# ETHERNET.net
KiCad netlist of a schematic drawn in Altium Designer
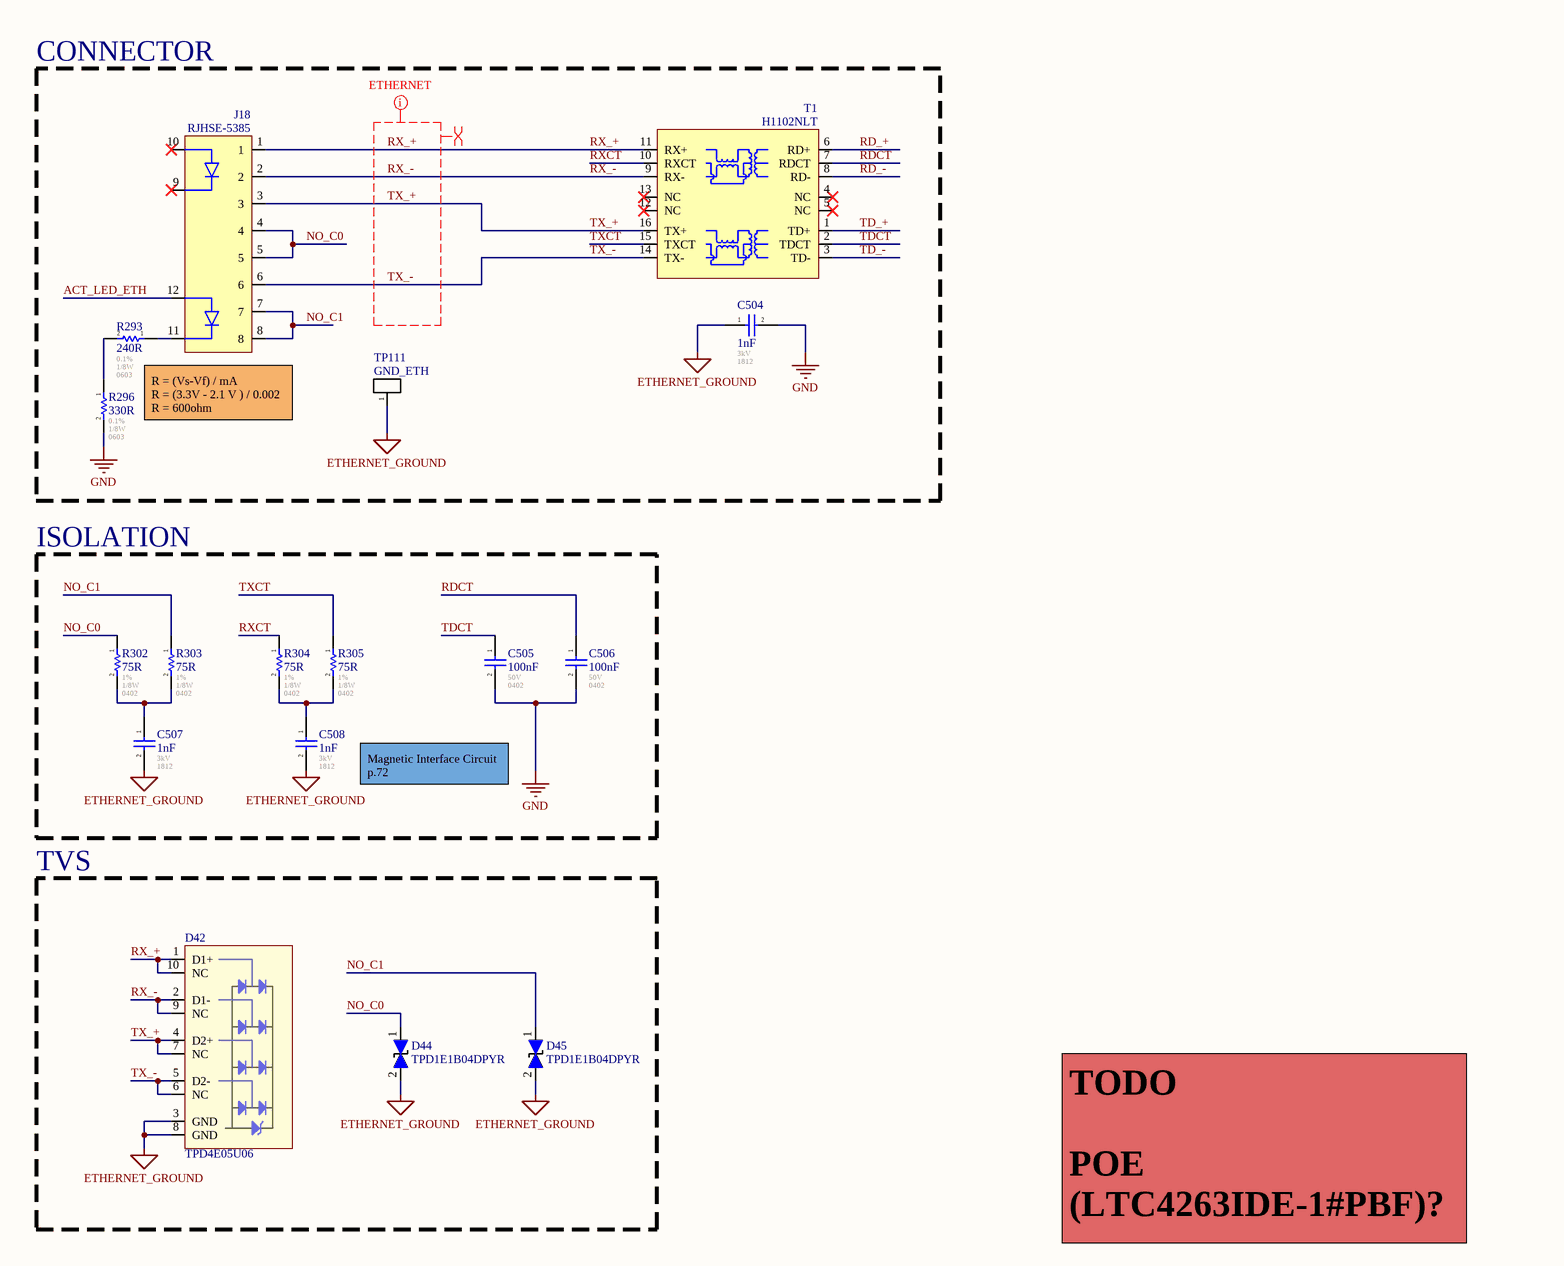
[diagram p0: ETHERNET.SchDoc, top left]
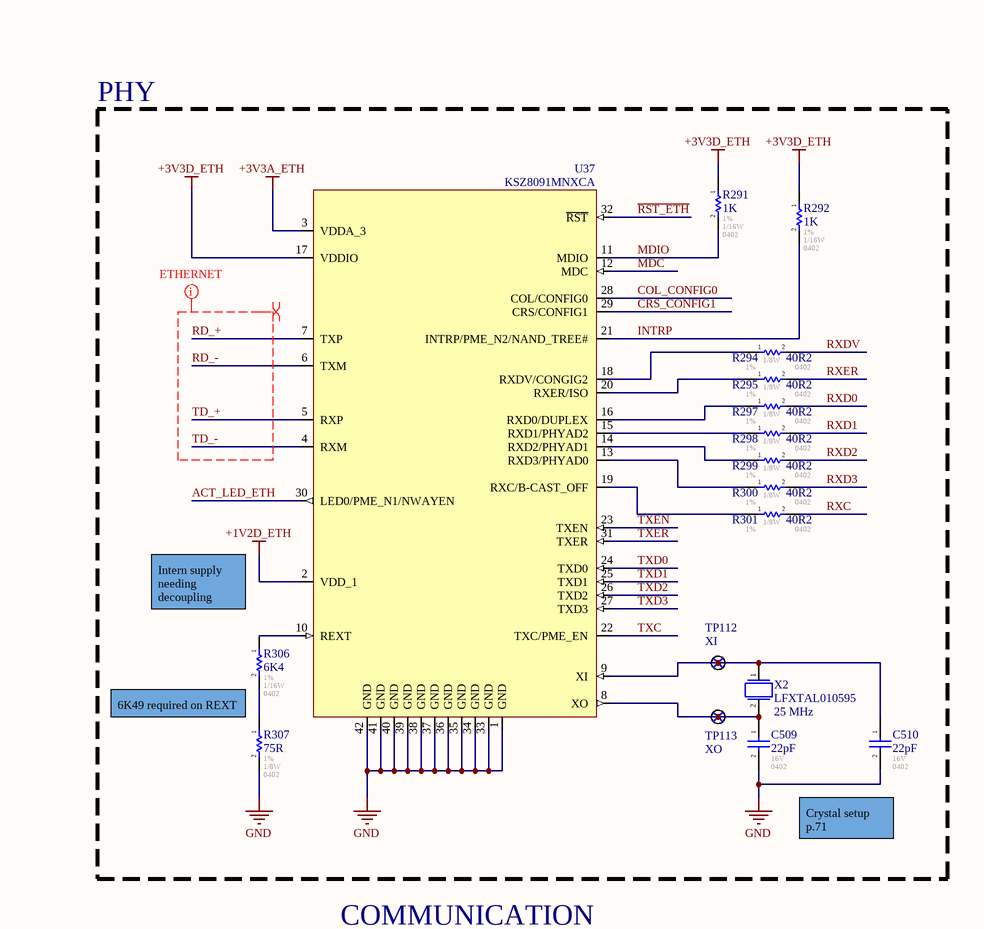
[diagram p1: ETHERNET.SchDoc, top right]
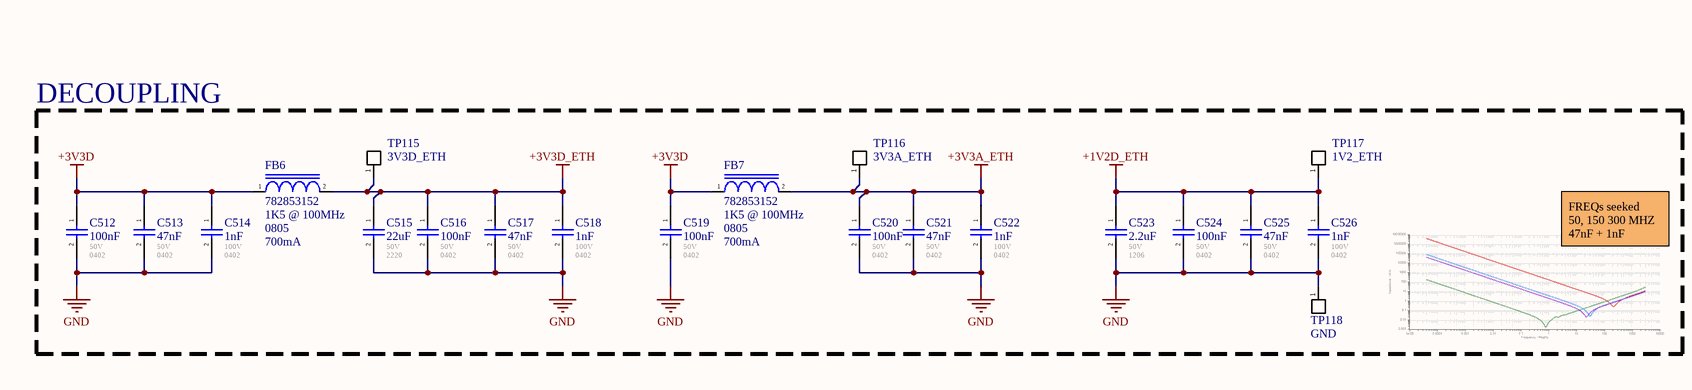
[diagram p2: ETHERNET.SchDoc, bottom left]
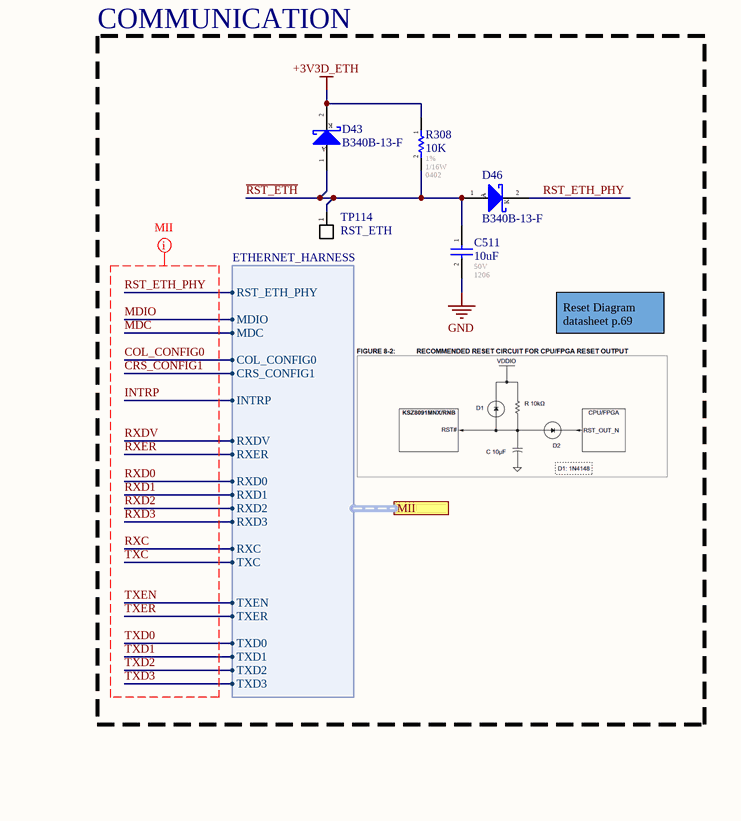
[diagram p3: ETHERNET.SchDoc, bottom right]

(export (version "E")
  (design (tool "Eeschema 10.0.6"))
  (components
    (comp (ref "C504")
      (value "1nF")
      (footprint "1812")
      (description "C1812C102KHRACAUTO\r\n0402 470pF 10% X7R Ceramic Capacitor")
      (fields
        (field (name "MFR") "KEMET")
        (field (name "PART#") "C1812C102KHRACAUTO")
        (field (name "VOLTAGE - RATED") "3kV")
      )
      (libsource (lib "Symbols") (part "CAP_CER"))
    )
    (comp (ref "C505")
      (value "100nF")
      (footprint "0402")
      (description "GCM155R71H104KE02J\r\n0402 100nF 10% X7R Ceramic Capacitor")
      (fields
        (field (name "MFR") "Murata")
        (field (name "PART#") "GCM155R71H104KE02J")
        (field (name "VOLTAGE - RATED") "50V")
      )
      (libsource (lib "Symbols") (part "CAP_CER"))
    )
    (comp (ref "C506")
      (value "100nF")
      (footprint "0402")
      (description "GCM155R71H104KE02J\r\n0402 100nF 10% X7R Ceramic Capacitor")
      (fields
        (field (name "MFR") "Murata")
        (field (name "PART#") "GCM155R71H104KE02J")
        (field (name "VOLTAGE - RATED") "50V")
      )
      (libsource (lib "Symbols") (part "CAP_CER"))
    )
    (comp (ref "C507")
      (value "1nF")
      (footprint "1812")
      (description "C1812C102KHRACAUTO\r\n0402 470pF 10% X7R Ceramic Capacitor")
      (fields
        (field (name "MFR") "KEMET")
        (field (name "PART#") "C1812C102KHRACAUTO")
        (field (name "VOLTAGE - RATED") "3kV")
      )
      (libsource (lib "Symbols") (part "CAP_CER"))
    )
    (comp (ref "C508")
      (value "1nF")
      (footprint "1812")
      (description "C1812C102KHRACAUTO\r\n0402 470pF 10% X7R Ceramic Capacitor")
      (fields
        (field (name "MFR") "KEMET")
        (field (name "PART#") "C1812C102KHRACAUTO")
        (field (name "VOLTAGE - RATED") "3kV")
      )
      (libsource (lib "Symbols") (part "CAP_CER"))
    )
    (comp (ref "C509")
      (value "22pF")
      (footprint "0402")
      (description "0402 22pF X7R Ceramic Capacitor\r\nC0402C220K4RACAUTO")
      (fields (field (name "VOLTAGE - RATED") "16V"))
      (libsource (lib "Symbols") (part "CAP_CER"))
    )
    (comp (ref "C510")
      (value "22pF")
      (footprint "0402")
      (description "0402 22pF X7R Ceramic Capacitor\r\nC0402C220K4RACAUTO")
      (fields (field (name "VOLTAGE - RATED") "16V"))
      (libsource (lib "Symbols") (part "CAP_CER"))
    )
    (comp (ref "C511")
      (value "10uF")
      (footprint "1206")
      (description "GRT31CR61H106KE01L\r\n1206 10uF 10% X5R Ceramic Capacitor")
      (fields
        (field (name "MFR") "Murata")
        (field (name "VOLTAGE - RATED") "50V")
        (field (name "TOLERANCE") "10%")
      )
      (libsource (lib "Symbols") (part "CAP_CER"))
    )
    (comp (ref "C512")
      (value "100nF")
      (footprint "0402")
      (description "GCM155R71H104KE02J\r\n0402 100nF 10% X7R Ceramic Capacitor")
      (fields
        (field (name "MFR") "Murata")
        (field (name "PART#") "GCM155R71H104KE02J")
        (field (name "VOLTAGE - RATED") "50V")
      )
      (libsource (lib "Symbols") (part "CAP_CER"))
    )
    (comp (ref "C513")
      (value "47nF")
      (footprint "0402")
      (description "GCM155R71H473KE02J\r\n0402 47nF 10% X7R Ceramic Capacitor")
      (fields
        (field (name "MFR") "Murata")
        (field (name "PART#") "GCM155R71H473KE02J")
        (field (name "VOLTAGE - RATED") "50V")
      )
      (libsource (lib "Symbols") (part "CAP_CER"))
    )
    (comp (ref "C514")
      (value "1nF")
      (footprint "0402")
      (description "GCM155R72A102KA37D\r\n0402 1nF 10% X7R Ceramic Capacitor")
      (fields
        (field (name "MFR") "Murata")
        (field (name "PART#") "GCM155R72A102KA37D")
        (field (name "VOLTAGE - RATED") "100V")
      )
      (libsource (lib "Symbols") (part "CAP_CER"))
    )
    (comp (ref "C515")
      (value "22uF")
      (footprint "2220")
      (description "CGA9P3X7R1H226M250KB\r\n2220 22uF 20% X7R Ceramic Capacitor")
      (fields
        (field (name "MFR") "TDK")
        (field (name "VOLTAGE - RATED") "50V")
        (field (name "TOLERANCE") "20%")
      )
      (libsource (lib "Symbols") (part "CAP_CER"))
    )
    (comp (ref "C516")
      (value "100nF")
      (footprint "0402")
      (description "GCM155R71H104KE02J\r\n0402 100nF 10% X7R Ceramic Capacitor")
      (fields
        (field (name "MFR") "Murata")
        (field (name "PART#") "GCM155R71H104KE02J")
        (field (name "VOLTAGE - RATED") "50V")
      )
      (libsource (lib "Symbols") (part "CAP_CER"))
    )
    (comp (ref "C517")
      (value "47nF")
      (footprint "0402")
      (description "GCM155R71H473KE02J\r\n0402 47nF 10% X7R Ceramic Capacitor")
      (fields
        (field (name "MFR") "Murata")
        (field (name "PART#") "GCM155R71H473KE02J")
        (field (name "VOLTAGE - RATED") "50V")
      )
      (libsource (lib "Symbols") (part "CAP_CER"))
    )
    (comp (ref "C518")
      (value "1nF")
      (footprint "0402")
      (description "GCM155R72A102KA37D\r\n0402 1nF 10% X7R Ceramic Capacitor")
      (fields
        (field (name "MFR") "Murata")
        (field (name "PART#") "GCM155R72A102KA37D")
        (field (name "VOLTAGE - RATED") "100V")
      )
      (libsource (lib "Symbols") (part "CAP_CER"))
    )
    (comp (ref "C519")
      (value "100nF")
      (footprint "0402")
      (description "GCM155R71H104KE02J\r\n0402 100nF 10% X7R Ceramic Capacitor")
      (fields
        (field (name "MFR") "Murata")
        (field (name "PART#") "GCM155R71H104KE02J")
        (field (name "VOLTAGE - RATED") "50V")
      )
      (libsource (lib "Symbols") (part "CAP_CER"))
    )
    (comp (ref "C520")
      (value "100nF")
      (footprint "0402")
      (description "GCM155R71H104KE02J\r\n0402 100nF 10% X7R Ceramic Capacitor")
      (fields
        (field (name "MFR") "Murata")
        (field (name "PART#") "GCM155R71H104KE02J")
        (field (name "VOLTAGE - RATED") "50V")
      )
      (libsource (lib "Symbols") (part "CAP_CER"))
    )
    (comp (ref "C521")
      (value "47nF")
      (footprint "0402")
      (description "GCM155R71H473KE02J\r\n0402 47nF 10% X7R Ceramic Capacitor")
      (fields
        (field (name "MFR") "Murata")
        (field (name "PART#") "GCM155R71H473KE02J")
        (field (name "VOLTAGE - RATED") "50V")
      )
      (libsource (lib "Symbols") (part "CAP_CER"))
    )
    (comp (ref "C522")
      (value "1nF")
      (footprint "0402")
      (description "GCM155R72A102KA37D\r\n0402 1nF 10% X7R Ceramic Capacitor")
      (fields
        (field (name "MFR") "Murata")
        (field (name "PART#") "GCM155R72A102KA37D")
        (field (name "VOLTAGE - RATED") "100V")
      )
      (libsource (lib "Symbols") (part "CAP_CER"))
    )
    (comp (ref "C523")
      (value "2.2uF")
      (footprint "1206")
      (description "GRT31CR71H225KE13L\r\n1206 2.2uF 10% X7R Ceramic Capacitor")
      (fields
        (field (name "MFR") "Murata")
        (field (name "PART#") "GRT31CR71H225KE13L")
        (field (name "VOLTAGE - RATED") "50V")
      )
      (libsource (lib "Symbols") (part "CAP_CER"))
    )
    (comp (ref "C524")
      (value "100nF")
      (footprint "0402")
      (description "GCM155R71H104KE02J\r\n0402 100nF 10% X7R Ceramic Capacitor")
      (fields
        (field (name "MFR") "Murata")
        (field (name "PART#") "GCM155R71H104KE02J")
        (field (name "VOLTAGE - RATED") "50V")
      )
      (libsource (lib "Symbols") (part "CAP_CER"))
    )
    (comp (ref "C525")
      (value "47nF")
      (footprint "0402")
      (description "GCM155R71H473KE02J\r\n0402 47nF 10% X7R Ceramic Capacitor")
      (fields
        (field (name "MFR") "Murata")
        (field (name "PART#") "GCM155R71H473KE02J")
        (field (name "VOLTAGE - RATED") "50V")
      )
      (libsource (lib "Symbols") (part "CAP_CER"))
    )
    (comp (ref "C526")
      (value "1nF")
      (footprint "0402")
      (description "GCM155R72A102KA37D\r\n0402 1nF 10% X7R Ceramic Capacitor")
      (fields
        (field (name "MFR") "Murata")
        (field (name "PART#") "GCM155R72A102KA37D")
        (field (name "VOLTAGE - RATED") "100V")
      )
      (libsource (lib "Symbols") (part "CAP_CER"))
    )
    (comp (ref "D42")
      (value "TPD4E05U06")
      (footprint "TVS_DATA_TPD4E05U06")
      (description "TVS - TVS DIODE 5.5VWM 14VC - 10SON")
      (fields
        (field (name "CREATEDBY/DATE") "Olivier Bernard / 12/3/2018")
        (field (name "VERIFIEDBY") "Caroline Paulin / 4 juillet 2018")
      )
      (libsource (lib "S7CAS_LIB2023") (part "TVS_DATA_TPD4E05U06"))
    )
    (comp (ref "D43")
      (value "B340B-13-F")
      (footprint "DO214AA (SMB)")
      (description "VS-15MQ040HM3/5AT")
      (libsource (lib "Symbols") (part "DIODE_SHOTTKEY"))
    )
    (comp (ref "D44")
      (value "TPD1E1B04DPYR")
      (footprint "TVS_DATA_TPD1E1B04DPYR")
      (description "TVS - TVS DIODE 3.6V 8.5V - 0402")
      (fields
        (field (name "CREATEDBY/DATE") "Keven Deslandes - 2018/10/19")
        (field (name "VERIFIEDBY") "Caroline Paulin - 28 janv 2019")
      )
      (libsource (lib "S7CAS_LIB2023") (part "TVS_DATA_TPD1E1B04DPYR"))
    )
    (comp (ref "D45")
      (value "TPD1E1B04DPYR")
      (footprint "TVS_DATA_TPD1E1B04DPYR")
      (description "TVS - TVS DIODE 3.6V 8.5V - 0402")
      (fields
        (field (name "CREATEDBY/DATE") "Keven Deslandes - 2018/10/19")
        (field (name "VERIFIEDBY") "Caroline Paulin - 28 janv 2019")
      )
      (libsource (lib "S7CAS_LIB2023") (part "TVS_DATA_TPD1E1B04DPYR"))
    )
    (comp (ref "D46")
      (value "B340B-13-F")
      (footprint "DO214AA (SMB)")
      (description "VS-15MQ040HM3/5AT")
      (libsource (lib "Symbols") (part "DIODE_SHOTTKEY"))
    )
    (comp (ref "FB6")
      (value "782853152")
      (footprint "IND_0805")
      (description "600 Ohms @ 100 MHz 1 Signal Line Ferrite Bead 0603 (1608 Metric) 1A 200mOhm")
      (fields
        (field (name "IMPEDANCE @ FREQ") "1K5 @ 100MHz")
        (field (name "PACKAGE / CASE") "0805")
        (field (name "CURRENT RATING") "700mA")
        (field (name "MANUFACTURER") "Wurth Elektronik")
      )
      (libsource (lib "Symbols") (part "FERRITE_BEAD"))
    )
    (comp (ref "FB7")
      (value "782853152")
      (footprint "IND_0805")
      (description "600 Ohms @ 100 MHz 1 Signal Line Ferrite Bead 0603 (1608 Metric) 1A 200mOhm")
      (fields
        (field (name "IMPEDANCE @ FREQ") "1K5 @ 100MHz")
        (field (name "PACKAGE / CASE") "0805")
        (field (name "CURRENT RATING") "700mA")
        (field (name "MANUFACTURER") "Wurth Elektronik")
      )
      (libsource (lib "Symbols") (part "FERRITE_BEAD"))
    )
    (comp (ref "J18")
      (value "RJHSE-5385")
      (footprint "CONN_ETHERNET_RJHSE-5385")
      (description "CONN - MOD JACK RJ45 R/A ETHERNET - TH")
      (fields (field (name "MFG") "Amphenol") (field (name "CREATEDBY") "Jonathan Bouchard"))
      (libsource (lib "S7CAS_LIB2023") (part "CONN_ETHERNET_RJHSE-5385"))
    )
    (comp (ref "R291")
      (value "1K")
      (footprint "RES_0402")
      (fields
        (field (name "TOLERANCE") "1%")
        (field (name "POWER") "1/16W")
        (field (name "PACKAGE / CASE") "0402")
      )
      (libsource (lib "Symbols") (part "RESISTOR"))
    )
    (comp (ref "R292")
      (value "1K")
      (footprint "RES_0402")
      (fields
        (field (name "TOLERANCE") "1%")
        (field (name "POWER") "1/16W")
        (field (name "PACKAGE / CASE") "0402")
      )
      (libsource (lib "Symbols") (part "RESISTOR"))
    )
    (comp (ref "R293")
      (value "240R")
      (footprint "RES_0603")
      (fields
        (field (name "TOLERANCE") "0.1%")
        (field (name "POWER") "1/8W")
        (field (name "PACKAGE / CASE") "0603")
      )
      (libsource (lib "Symbols") (part "RESISTOR"))
    )
    (comp (ref "R294")
      (value "40R2")
      (footprint "RES_0402")
      (fields
        (field (name "TOLERANCE") "1%")
        (field (name "POWER") "1/8W")
        (field (name "PACKAGE / CASE") "0402")
      )
      (libsource (lib "Symbols") (part "RESISTOR"))
    )
    (comp (ref "R295")
      (value "40R2")
      (footprint "RES_0402")
      (fields
        (field (name "TOLERANCE") "1%")
        (field (name "POWER") "1/8W")
        (field (name "PACKAGE / CASE") "0402")
      )
      (libsource (lib "Symbols") (part "RESISTOR"))
    )
    (comp (ref "R296")
      (value "330R")
      (footprint "RES_0603")
      (description "1M 0603 1% 1/16W Resistor")
      (fields
        (field (name "TOLERANCE") "0.1%")
        (field (name "POWER") "1/8W")
        (field (name "PACKAGE / CASE") "0603")
      )
      (libsource (lib "Symbols") (part "RESISTOR"))
    )
    (comp (ref "R297")
      (value "40R2")
      (footprint "RES_0402")
      (fields
        (field (name "TOLERANCE") "1%")
        (field (name "POWER") "1/8W")
        (field (name "PACKAGE / CASE") "0402")
      )
      (libsource (lib "Symbols") (part "RESISTOR"))
    )
    (comp (ref "R298")
      (value "40R2")
      (footprint "RES_0402")
      (fields
        (field (name "TOLERANCE") "1%")
        (field (name "POWER") "1/8W")
        (field (name "PACKAGE / CASE") "0402")
      )
      (libsource (lib "Symbols") (part "RESISTOR"))
    )
    (comp (ref "R299")
      (value "40R2")
      (footprint "RES_0402")
      (fields
        (field (name "TOLERANCE") "1%")
        (field (name "POWER") "1/8W")
        (field (name "PACKAGE / CASE") "0402")
      )
      (libsource (lib "Symbols") (part "RESISTOR"))
    )
    (comp (ref "R300")
      (value "40R2")
      (footprint "RES_0402")
      (fields
        (field (name "TOLERANCE") "1%")
        (field (name "POWER") "1/8W")
        (field (name "PACKAGE / CASE") "0402")
      )
      (libsource (lib "Symbols") (part "RESISTOR"))
    )
    (comp (ref "R301")
      (value "40R2")
      (footprint "RES_0402")
      (fields
        (field (name "TOLERANCE") "1%")
        (field (name "POWER") "1/8W")
        (field (name "PACKAGE / CASE") "0402")
      )
      (libsource (lib "Symbols") (part "RESISTOR"))
    )
    (comp (ref "R302")
      (value "75R")
      (footprint "RES_0402")
      (fields
        (field (name "TOLERANCE") "1%")
        (field (name "POWER") "1/8W")
        (field (name "PACKAGE / CASE") "0402")
      )
      (libsource (lib "Symbols") (part "RESISTOR"))
    )
    (comp (ref "R303")
      (value "75R")
      (footprint "RES_0402")
      (fields
        (field (name "TOLERANCE") "1%")
        (field (name "POWER") "1/8W")
        (field (name "PACKAGE / CASE") "0402")
      )
      (libsource (lib "Symbols") (part "RESISTOR"))
    )
    (comp (ref "R304")
      (value "75R")
      (footprint "RES_0402")
      (fields
        (field (name "TOLERANCE") "1%")
        (field (name "POWER") "1/8W")
        (field (name "PACKAGE / CASE") "0402")
      )
      (libsource (lib "Symbols") (part "RESISTOR"))
    )
    (comp (ref "R305")
      (value "75R")
      (footprint "RES_0402")
      (fields
        (field (name "TOLERANCE") "1%")
        (field (name "POWER") "1/8W")
        (field (name "PACKAGE / CASE") "0402")
      )
      (libsource (lib "Symbols") (part "RESISTOR"))
    )
    (comp (ref "R306")
      (value "6K4")
      (footprint "RES_0402")
      (fields
        (field (name "TOLERANCE") "1%")
        (field (name "POWER") "1/16W")
        (field (name "PACKAGE / CASE") "0402")
      )
      (libsource (lib "Symbols") (part "RESISTOR"))
    )
    (comp (ref "R307")
      (value "75R")
      (footprint "RES_0402")
      (fields
        (field (name "TOLERANCE") "1%")
        (field (name "POWER") "1/8W")
        (field (name "PACKAGE / CASE") "0402")
      )
      (libsource (lib "Symbols") (part "RESISTOR"))
    )
    (comp (ref "R308")
      (value "10K")
      (footprint "RES_0402")
      (fields
        (field (name "TOLERANCE") "1%")
        (field (name "POWER") "1/16W")
        (field (name "PACKAGE / CASE") "0402")
      )
      (libsource (lib "Symbols") (part "RESISTOR"))
    )
    (comp (ref "T1")
      (value "H1102NLT")
      (footprint "TRANSFO_H1102NLT")
      (description "TRANSFO - ETHERNET 10/100B-TX - SMD-16")
      (fields (field (name "MFG") "Pulse Eng.") (field (name "CREATEDBY") "Jonathan Bouchard"))
      (libsource (lib "S7CAS_LIB2023") (part "TRANSFO_H1102NLT"))
    )
    (comp (ref "TP111")
      (value "GND_ETH")
      (footprint "TP_HOLE")
      (description "Test Point")
      (libsource (lib "Symbols") (part "TESTPOINT"))
    )
    (comp (ref "TP112")
      (value "XI")
      (footprint "TP_PAD_TINY")
      (description "Test Point")
      (libsource (lib "Symbols") (part "TESTPOINT_PAD_TINY"))
    )
    (comp (ref "TP113")
      (value "XO")
      (footprint "TP_PAD_TINY")
      (description "Test Point")
      (libsource (lib "Symbols") (part "TESTPOINT_PAD_TINY"))
    )
    (comp (ref "TP114")
      (value "RST_ETH")
      (footprint "TP_PAD")
      (description "Test Point")
      (libsource (lib "Symbols") (part "TESTPOINT_PAD"))
    )
    (comp (ref "TP115")
      (value "3V3D_ETH")
      (footprint "TP_PAD")
      (description "Test Point")
      (libsource (lib "Symbols") (part "TESTPOINT_PAD"))
    )
    (comp (ref "TP116")
      (value "3V3A_ETH")
      (footprint "TP_PAD")
      (description "Test Point")
      (libsource (lib "Symbols") (part "TESTPOINT_PAD"))
    )
    (comp (ref "TP117")
      (value "1V2_ETH")
      (footprint "TP_PAD")
      (description "Test Point")
      (libsource (lib "Symbols") (part "TESTPOINT_PAD"))
    )
    (comp (ref "TP118")
      (value "GND")
      (footprint "TP_PAD")
      (description "Test Point")
      (libsource (lib "Symbols") (part "TESTPOINT_PAD"))
    )
    (comp (ref "U37")
      (value "KSZ8091MNXCA")
      (footprint "COM_ETH_PHY_KSZ8091MNXCA")
      (description "COM - ETHERNET PHY 10/100 - QFN-32")
      (fields
        (field (name "VOLTAGE") "1.8V, 2.5V, 3.3V")
        (field (name "MFG") "Micrel")
        (field (name "CREATEDBY") "Jonathan Bouchard")
      )
      (libsource (lib "S7CAS_LIB2023") (part "COM_ETH_PHY_KSZ8091MNXCA"))
    )
    (comp (ref "X2")
      (value "LFXTAL010595")
      (footprint "HC49_SMD")
      (description "25 MHz ±30ppm Crystal 16pF 40 Ohms HC-49/US")
      (fields (field (name "FREQUENCY") "25 MHz"))
      (libsource (lib "Symbols") (part "OSCILLATOR"))
    )
  )
  (nets
    (net (code "2") (name "+1V2D_ETH") (class "Default")
      (node (ref "C523") (pin "1") (pinfunction "1_1") (pintype "passive"))
      (node (ref "C524") (pin "1") (pinfunction "1_1") (pintype "passive"))
      (node (ref "C525") (pin "1") (pinfunction "1_1") (pintype "passive"))
      (node (ref "C526") (pin "1") (pinfunction "1_1") (pintype "passive"))
      (node (ref "TP117") (pin "1") (pinfunction "A_1") (pintype "passive"))
      (node (ref "U37") (pin "2") (pinfunction "VDD_1_2") (pintype "power_in"))
    )
    (net (code "3") (name "+3V3A_ETH") (class "Default")
      (node (ref "C520") (pin "1") (pinfunction "1_1") (pintype "passive"))
      (node (ref "C521") (pin "1") (pinfunction "1_1") (pintype "passive"))
      (node (ref "C522") (pin "1") (pinfunction "1_1") (pintype "passive"))
      (node (ref "FB7") (pin "2") (pinfunction "2_2") (pintype "passive"))
      (node (ref "TP116") (pin "1") (pinfunction "A_1") (pintype "passive"))
      (node (ref "U37") (pin "3") (pinfunction "VDDA_3_3") (pintype "power_in"))
    )
    (net (code "4") (name "+3V3D") (class "Default")
      (node (ref "C512") (pin "1") (pinfunction "1_1") (pintype "passive"))
      (node (ref "C513") (pin "1") (pinfunction "1_1") (pintype "passive"))
      (node (ref "C514") (pin "1") (pinfunction "1_1") (pintype "passive"))
      (node (ref "C519") (pin "1") (pinfunction "1_1") (pintype "passive"))
      (node (ref "FB6") (pin "1") (pinfunction "1_1") (pintype "passive"))
      (node (ref "FB7") (pin "1") (pinfunction "1_1") (pintype "passive"))
    )
    (net (code "5") (name "+3V3D_ETH") (class "Default")
      (node (ref "C515") (pin "1") (pinfunction "1_1") (pintype "passive"))
      (node (ref "C516") (pin "1") (pinfunction "1_1") (pintype "passive"))
      (node (ref "C517") (pin "1") (pinfunction "1_1") (pintype "passive"))
      (node (ref "C518") (pin "1") (pinfunction "1_1") (pintype "passive"))
      (node (ref "D43") (pin "2") (pinfunction "K_2") (pintype "passive"))
      (node (ref "FB6") (pin "2") (pinfunction "2_2") (pintype "passive"))
      (node (ref "R291") (pin "1") (pinfunction "1_1") (pintype "passive"))
      (node (ref "R292") (pin "1") (pinfunction "1_1") (pintype "passive"))
      (node (ref "R308") (pin "1") (pinfunction "1_1") (pintype "passive"))
      (node (ref "TP115") (pin "1") (pinfunction "A_1") (pintype "passive"))
      (node (ref "U37") (pin "17") (pinfunction "VDDIO_17") (pintype "power_in"))
    )
    (net (code "6") (name "/ACT_LED_ETH") (class "Default")
      (node (ref "J18") (pin "12") (pinfunction "LED2_A_12") (pintype "passive"))
      (node (ref "U37") (pin "30") (pinfunction "LED0/PME_N1/NWAYEN_30") (pintype "output"))
    )
    (net (code "7") (name "/COL_CONFIG0") (class "Default")
      (node (ref "U37") (pin "28") (pinfunction "COL/CONFIG0_28") (pintype "bidirectional"))
    )
    (net (code "8") (name "/CRS_CONFIG1") (class "Default")
      (node (ref "U37") (pin "29") (pinfunction "CRS/CONFIG1_29") (pintype "bidirectional"))
    )
    (net (code "9") (name "/INTRP") (class "Default")
      (node (ref "R292") (pin "2") (pinfunction "2_2") (pintype "passive"))
      (node (ref "U37") (pin "21") (pinfunction "INTRP/PME_N2/NAND_TREE#_21") (pintype "bidirectional"))
    )
    (net (code "10") (name "/MDC") (class "Default")
      (node (ref "U37") (pin "12") (pinfunction "MDC_12") (pintype "input"))
    )
    (net (code "11") (name "/MDIO") (class "Default")
      (node (ref "R291") (pin "2") (pinfunction "2_2") (pintype "passive"))
      (node (ref "U37") (pin "11") (pinfunction "MDIO_11") (pintype "bidirectional"))
    )
    (net (code "12") (name "/NO_C0") (class "Default")
      (node (ref "D44") (pin "1") (pinfunction "i/o_1") (pintype "passive"))
      (node (ref "J18") (pin "4") (pinfunction "4_4") (pintype "passive"))
      (node (ref "J18") (pin "5") (pinfunction "5_5") (pintype "passive"))
      (node (ref "R302") (pin "1") (pinfunction "1_1") (pintype "passive"))
    )
    (net (code "13") (name "/NO_C1") (class "Default")
      (node (ref "D45") (pin "1") (pinfunction "i/o_1") (pintype "passive"))
      (node (ref "J18") (pin "7") (pinfunction "7_7") (pintype "passive"))
      (node (ref "J18") (pin "8") (pinfunction "8_8") (pintype "passive"))
      (node (ref "R303") (pin "1") (pinfunction "1_1") (pintype "passive"))
    )
    (net (code "14") (name "/RDCT") (class "Default")
      (node (ref "C506") (pin "1") (pinfunction "1_1") (pintype "passive"))
      (node (ref "T1") (pin "7") (pinfunction "RDCT_7") (pintype "passive"))
    )
    (net (code "15") (name "/RD_+") (class "Default")
      (node (ref "T1") (pin "6") (pinfunction "RD+_6") (pintype "passive"))
      (node (ref "U37") (pin "7") (pinfunction "TXP_7") (pintype "bidirectional"))
    )
    (net (code "16") (name "/RD_-") (class "Default")
      (node (ref "T1") (pin "8") (pinfunction "RD-_8") (pintype "passive"))
      (node (ref "U37") (pin "6") (pinfunction "TXM_6") (pintype "bidirectional"))
    )
    (net (code "17") (name "/RST_ETH") (class "Default")
      (node (ref "C511") (pin "1") (pinfunction "1_1") (pintype "passive"))
      (node (ref "D43") (pin "1") (pinfunction "A_1") (pintype "passive"))
      (node (ref "D46") (pin "1") (pinfunction "A_1") (pintype "passive"))
      (node (ref "R308") (pin "2") (pinfunction "2_2") (pintype "passive"))
      (node (ref "TP114") (pin "1") (pinfunction "A_1") (pintype "passive"))
      (node (ref "U37") (pin "32") (pinfunction "RST_32") (pintype "input"))
    )
    (net (code "18") (name "/RST_ETH_PHY") (class "Default")
      (node (ref "D46") (pin "2") (pinfunction "K_2") (pintype "passive"))
    )
    (net (code "19") (name "/RXC") (class "Default")
      (node (ref "R301") (pin "2") (pinfunction "2_2") (pintype "passive"))
    )
    (net (code "20") (name "/RXCT") (class "Default")
      (node (ref "R304") (pin "1") (pinfunction "1_1") (pintype "passive"))
      (node (ref "T1") (pin "10") (pinfunction "RXCT_10") (pintype "passive"))
    )
    (net (code "21") (name "/RXD0") (class "Default")
      (node (ref "R297") (pin "2") (pinfunction "2_2") (pintype "passive"))
    )
    (net (code "22") (name "/RXD1") (class "Default")
      (node (ref "R298") (pin "2") (pinfunction "2_2") (pintype "passive"))
    )
    (net (code "23") (name "/RXD2") (class "Default")
      (node (ref "R299") (pin "2") (pinfunction "2_2") (pintype "passive"))
    )
    (net (code "24") (name "/RXD3") (class "Default")
      (node (ref "R300") (pin "2") (pinfunction "2_2") (pintype "passive"))
    )
    (net (code "25") (name "/RXDV") (class "Default")
      (node (ref "R294") (pin "2") (pinfunction "2_2") (pintype "passive"))
    )
    (net (code "26") (name "/RXER") (class "Default")
      (node (ref "R295") (pin "2") (pinfunction "2_2") (pintype "passive"))
    )
    (net (code "27") (name "/RX_+") (class "Default")
      (node (ref "D42") (pin "1") (pinfunction "D1+_1") (pintype "passive"))
      (node (ref "D42") (pin "10") (pinfunction "NC_10") (pintype "passive"))
      (node (ref "J18") (pin "1") (pinfunction "1_1") (pintype "passive"))
      (node (ref "T1") (pin "11") (pinfunction "RX+_11") (pintype "passive"))
    )
    (net (code "28") (name "/RX_-") (class "Default")
      (node (ref "D42") (pin "2") (pinfunction "D1-_2") (pintype "passive"))
      (node (ref "D42") (pin "9") (pinfunction "NC_9") (pintype "passive"))
      (node (ref "J18") (pin "2") (pinfunction "2_2") (pintype "passive"))
      (node (ref "T1") (pin "9") (pinfunction "RX-_9") (pintype "passive"))
    )
    (net (code "29") (name "/TDCT") (class "Default")
      (node (ref "C505") (pin "1") (pinfunction "1_1") (pintype "passive"))
      (node (ref "T1") (pin "2") (pinfunction "TDCT_2") (pintype "passive"))
    )
    (net (code "30") (name "/TD_+") (class "Default")
      (node (ref "T1") (pin "1") (pinfunction "TD+_1") (pintype "passive"))
      (node (ref "U37") (pin "5") (pinfunction "RXP_5") (pintype "bidirectional"))
    )
    (net (code "31") (name "/TD_-") (class "Default")
      (node (ref "T1") (pin "3") (pinfunction "TD-_3") (pintype "passive"))
      (node (ref "U37") (pin "4") (pinfunction "RXM_4") (pintype "bidirectional"))
    )
    (net (code "32") (name "/TXC") (class "Default")
      (node (ref "U37") (pin "22") (pinfunction "TXC/PME_EN_22") (pintype "bidirectional"))
    )
    (net (code "33") (name "/TXCT") (class "Default")
      (node (ref "R305") (pin "1") (pinfunction "1_1") (pintype "passive"))
      (node (ref "T1") (pin "15") (pinfunction "TXCT_15") (pintype "passive"))
    )
    (net (code "34") (name "/TXD0") (class "Default")
      (node (ref "U37") (pin "24") (pinfunction "TXD0_24") (pintype "input"))
    )
    (net (code "35") (name "/TXD1") (class "Default")
      (node (ref "U37") (pin "25") (pinfunction "TXD1_25") (pintype "input"))
    )
    (net (code "36") (name "/TXD2") (class "Default")
      (node (ref "U37") (pin "26") (pinfunction "TXD2_26") (pintype "input"))
    )
    (net (code "37") (name "/TXD3") (class "Default")
      (node (ref "U37") (pin "27") (pinfunction "TXD3_27") (pintype "input"))
    )
    (net (code "38") (name "/TXEN") (class "Default")
      (node (ref "U37") (pin "23") (pinfunction "TXEN_23") (pintype "input"))
    )
    (net (code "39") (name "/TXER") (class "Default")
      (node (ref "U37") (pin "31") (pinfunction "TXER_31") (pintype "input"))
    )
    (net (code "40") (name "/TX_+") (class "Default")
      (node (ref "D42") (pin "4") (pinfunction "D2+_4") (pintype "passive"))
      (node (ref "D42") (pin "7") (pinfunction "NC_7") (pintype "passive"))
      (node (ref "J18") (pin "3") (pinfunction "3_3") (pintype "passive"))
      (node (ref "T1") (pin "16") (pinfunction "TX+_16") (pintype "passive"))
    )
    (net (code "41") (name "/TX_-") (class "Default")
      (node (ref "D42") (pin "5") (pinfunction "D2-_5") (pintype "passive"))
      (node (ref "D42") (pin "6") (pinfunction "NC_6") (pintype "passive"))
      (node (ref "J18") (pin "6") (pinfunction "6_6") (pintype "passive"))
      (node (ref "T1") (pin "14") (pinfunction "TX-_14") (pintype "passive"))
    )
    (net (code "43") (name "ETHERNET_GROUND") (class "Default")
      (node (ref "C504") (pin "1") (pinfunction "1_1") (pintype "passive"))
      (node (ref "C507") (pin "2") (pinfunction "2_2") (pintype "passive"))
      (node (ref "C508") (pin "2") (pinfunction "2_2") (pintype "passive"))
      (node (ref "D42") (pin "3") (pinfunction "GND_3") (pintype "passive"))
      (node (ref "D42") (pin "8") (pinfunction "GND_8") (pintype "passive"))
      (node (ref "D44") (pin "2") (pinfunction "i/o_2") (pintype "passive"))
      (node (ref "D45") (pin "2") (pinfunction "i/o_2") (pintype "passive"))
      (node (ref "TP111") (pin "1") (pinfunction "A_1") (pintype "passive"))
    )
    (net (code "44") (name "GND") (class "Default")
      (node (ref "C504") (pin "2") (pinfunction "2_2") (pintype "passive"))
      (node (ref "C505") (pin "2") (pinfunction "2_2") (pintype "passive"))
      (node (ref "C506") (pin "2") (pinfunction "2_2") (pintype "passive"))
      (node (ref "C509") (pin "2") (pinfunction "2_2") (pintype "passive"))
      (node (ref "C510") (pin "2") (pinfunction "2_2") (pintype "passive"))
      (node (ref "C511") (pin "2") (pinfunction "2_2") (pintype "passive"))
      (node (ref "C512") (pin "2") (pinfunction "2_2") (pintype "passive"))
      (node (ref "C513") (pin "2") (pinfunction "2_2") (pintype "passive"))
      (node (ref "C514") (pin "2") (pinfunction "2_2") (pintype "passive"))
      (node (ref "C515") (pin "2") (pinfunction "2_2") (pintype "passive"))
      (node (ref "C516") (pin "2") (pinfunction "2_2") (pintype "passive"))
      (node (ref "C517") (pin "2") (pinfunction "2_2") (pintype "passive"))
      (node (ref "C518") (pin "2") (pinfunction "2_2") (pintype "passive"))
      (node (ref "C519") (pin "2") (pinfunction "2_2") (pintype "passive"))
      (node (ref "C520") (pin "2") (pinfunction "2_2") (pintype "passive"))
      (node (ref "C521") (pin "2") (pinfunction "2_2") (pintype "passive"))
      (node (ref "C522") (pin "2") (pinfunction "2_2") (pintype "passive"))
      (node (ref "C523") (pin "2") (pinfunction "2_2") (pintype "passive"))
      (node (ref "C524") (pin "2") (pinfunction "2_2") (pintype "passive"))
      (node (ref "C525") (pin "2") (pinfunction "2_2") (pintype "passive"))
      (node (ref "C526") (pin "2") (pinfunction "2_2") (pintype "passive"))
      (node (ref "R296") (pin "2") (pinfunction "2_2") (pintype "passive"))
      (node (ref "R307") (pin "2") (pinfunction "2_2") (pintype "passive"))
      (node (ref "TP118") (pin "1") (pinfunction "A_1") (pintype "passive"))
      (node (ref "U37") (pin "1") (pinfunction "GND_1") (pintype "power_in"))
      (node (ref "U37") (pin "33") (pinfunction "GND_33") (pintype "power_in"))
      (node (ref "U37") (pin "34") (pinfunction "GND_34") (pintype "power_in"))
      (node (ref "U37") (pin "35") (pinfunction "GND_35") (pintype "power_in"))
      (node (ref "U37") (pin "36") (pinfunction "GND_36") (pintype "power_in"))
      (node (ref "U37") (pin "37") (pinfunction "GND_37") (pintype "power_in"))
      (node (ref "U37") (pin "38") (pinfunction "GND_38") (pintype "power_in"))
      (node (ref "U37") (pin "39") (pinfunction "GND_39") (pintype "power_in"))
      (node (ref "U37") (pin "40") (pinfunction "GND_40") (pintype "power_in"))
      (node (ref "U37") (pin "41") (pinfunction "GND_41") (pintype "power_in"))
      (node (ref "U37") (pin "42") (pinfunction "GND_42") (pintype "power_in"))
    )
    (net (code "45") (name "Net-(C507-Pad1)") (class "Default")
      (node (ref "C507") (pin "1") (pinfunction "1_1") (pintype "passive"))
      (node (ref "R302") (pin "2") (pinfunction "2_2") (pintype "passive"))
      (node (ref "R303") (pin "2") (pinfunction "2_2") (pintype "passive"))
    )
    (net (code "46") (name "Net-(C508-Pad1)") (class "Default")
      (node (ref "C508") (pin "1") (pinfunction "1_1") (pintype "passive"))
      (node (ref "R304") (pin "2") (pinfunction "2_2") (pintype "passive"))
      (node (ref "R305") (pin "2") (pinfunction "2_2") (pintype "passive"))
    )
    (net (code "47") (name "Net-(J18-LED2_K)") (class "Default")
      (node (ref "J18") (pin "11") (pinfunction "LED2_K_11") (pintype "passive"))
      (node (ref "R293") (pin "1") (pinfunction "1_1") (pintype "passive"))
    )
    (net (code "48") (name "Net-(R293-Pad2)") (class "Default")
      (node (ref "R293") (pin "2") (pinfunction "2_2") (pintype "passive"))
      (node (ref "R296") (pin "1") (pinfunction "1_1") (pintype "passive"))
    )
    (net (code "49") (name "Net-(R306-Pad2)") (class "Default")
      (node (ref "R306") (pin "2") (pinfunction "2_2") (pintype "passive"))
      (node (ref "R307") (pin "1") (pinfunction "1_1") (pintype "passive"))
    )
    (net (code "50") (name "Net-(TP112-A)") (class "Default")
      (node (ref "C510") (pin "1") (pinfunction "1_1") (pintype "passive"))
      (node (ref "TP112") (pin "1") (pinfunction "A_1") (pintype "passive"))
      (node (ref "U37") (pin "9") (pinfunction "XI_9") (pintype "input"))
      (node (ref "X2") (pin "1") (pinfunction "1_1") (pintype "passive"))
    )
    (net (code "51") (name "Net-(TP113-A)") (class "Default")
      (node (ref "C509") (pin "1") (pinfunction "1_1") (pintype "passive"))
      (node (ref "TP113") (pin "1") (pinfunction "A_1") (pintype "passive"))
      (node (ref "U37") (pin "8") (pinfunction "XO_8") (pintype "output"))
      (node (ref "X2") (pin "2") (pinfunction "2_2") (pintype "passive"))
    )
    (net (code "52") (name "Net-(U37-REXT)") (class "Default")
      (node (ref "R306") (pin "1") (pinfunction "1_1") (pintype "passive"))
      (node (ref "U37") (pin "10") (pinfunction "REXT_10") (pintype "input"))
    )
    (net (code "53") (name "Net-(U37-RXC{slash}B-CAST_OFF)") (class "Default")
      (node (ref "R301") (pin "1") (pinfunction "1_1") (pintype "passive"))
      (node (ref "U37") (pin "19") (pinfunction "RXC/B-CAST_OFF_19") (pintype "bidirectional"))
    )
    (net (code "54") (name "Net-(U37-RXD0{slash}DUPLEX)") (class "Default")
      (node (ref "R297") (pin "1") (pinfunction "1_1") (pintype "passive"))
      (node (ref "U37") (pin "16") (pinfunction "RXD0/DUPLEX_16") (pintype "bidirectional"))
    )
    (net (code "55") (name "Net-(U37-RXD1{slash}PHYAD2)") (class "Default")
      (node (ref "R298") (pin "1") (pinfunction "1_1") (pintype "passive"))
      (node (ref "U37") (pin "15") (pinfunction "RXD1/PHYAD2_15") (pintype "bidirectional"))
    )
    (net (code "56") (name "Net-(U37-RXD2{slash}PHYAD1)") (class "Default")
      (node (ref "R299") (pin "1") (pinfunction "1_1") (pintype "passive"))
      (node (ref "U37") (pin "14") (pinfunction "RXD2/PHYAD1_14") (pintype "bidirectional"))
    )
    (net (code "57") (name "Net-(U37-RXD3{slash}PHYAD0)") (class "Default")
      (node (ref "R300") (pin "1") (pinfunction "1_1") (pintype "passive"))
      (node (ref "U37") (pin "13") (pinfunction "RXD3/PHYAD0_13") (pintype "bidirectional"))
    )
    (net (code "58") (name "Net-(U37-RXDV{slash}CONGIG2)") (class "Default")
      (node (ref "R294") (pin "1") (pinfunction "1_1") (pintype "passive"))
      (node (ref "U37") (pin "18") (pinfunction "RXDV/CONGIG2_18") (pintype "bidirectional"))
    )
    (net (code "59") (name "Net-(U37-RXER{slash}ISO)") (class "Default")
      (node (ref "R295") (pin "1") (pinfunction "1_1") (pintype "passive"))
      (node (ref "U37") (pin "20") (pinfunction "RXER/ISO_20") (pintype "bidirectional"))
    )
    (net (code "60") (name "unconnected-(J18-LED1_A-Pad10)") (class "Default")
      (node (ref "J18") (pin "10") (pinfunction "LED1_A_10") (pintype "passive+no_connect"))
    )
    (net (code "61") (name "unconnected-(J18-LED1_K-Pad9)") (class "Default")
      (node (ref "J18") (pin "9") (pinfunction "LED1_K_9") (pintype "passive+no_connect"))
    )
    (net (code "62") (name "unconnected-(T1-NC-Pad4)") (class "Default")
      (node (ref "T1") (pin "4") (pinfunction "NC_4") (pintype "passive+no_connect"))
    )
    (net (code "63") (name "unconnected-(T1-NC-Pad5)") (class "Default")
      (node (ref "T1") (pin "5") (pinfunction "NC_5") (pintype "passive+no_connect"))
    )
    (net (code "64") (name "unconnected-(T1-NC-Pad12)") (class "Default")
      (node (ref "T1") (pin "12") (pinfunction "NC_12") (pintype "passive+no_connect"))
    )
    (net (code "65") (name "unconnected-(T1-NC-Pad13)") (class "Default")
      (node (ref "T1") (pin "13") (pinfunction "NC_13") (pintype "passive+no_connect"))
    )
  )
)
